# MCU2.net
KiCad netlist of a schematic drawn in Altium Designer
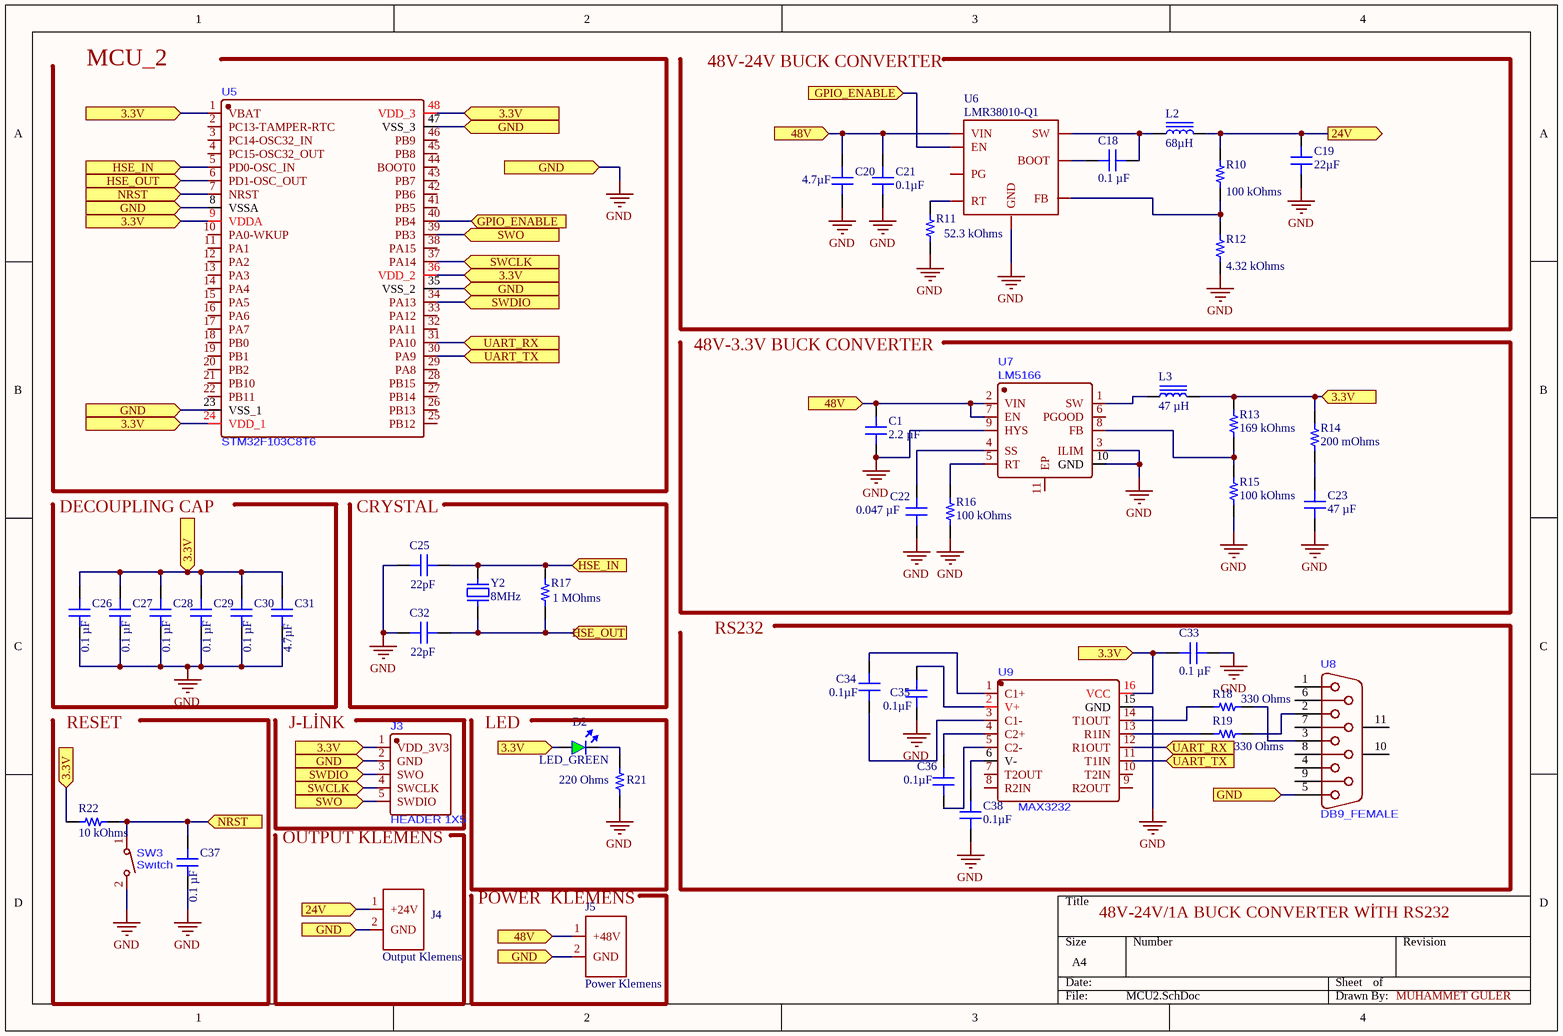
[diagram p0: MCU2.SchDoc]

(export (version "E")
  (design (tool "Eeschema 10.0.6"))
  (components
    (comp (ref "C1")
      (value "2.2 µF")
      (footprint "CAP 1210_3225 - 1MM")
      (description "CAP CER 2.2UF 100V X7R 1210")
      (fields
        (field (name "PART NUMBER") "1210BB225K101NGX085T")
        (field (name "MANUFACTURER") "Knowles Novacap")
      )
      (libsource (lib "Celestial Altium Library - altium_library") (part "Capacitor"))
    )
    (comp (ref "C18")
      (value "0.1 µF")
      (footprint "CAP 0603_1608")
      (description "CAP CER 0.1UF 50V X7R 0603")
      (fields (field (name "PART NUMBER") "C0603C104K5RAC7411"))
      (libsource (lib "Celestial Altium Library - altium_library") (part "Capacitor"))
    )
    (comp (ref "C19")
      (value "22µF")
      (footprint "CAP 1210_3225 - 2.8MM")
      (description "CAP CER 22UF 25V X5R 1210")
      (fields (field (name "PART NUMBER") "12103D226KAT2A") (field (name "MANUFACTURER") "AVX Corporation"))
      (libsource (lib "Celestial Altium Library - altium_library") (part "Capacitor"))
    )
    (comp (ref "C20")
      (value "4.7µF")
      (footprint "CAP 1210_3225 - 2.8MM")
      (description "CAP CER 4.7UF 100V X7R 1210")
      (fields (field (name "PART NUMBER") "12101C475K4T2A") (field (name "MANUFACTURER") "AVX Corporation"))
      (libsource (lib "Celestial Altium Library - altium_library") (part "Capacitor"))
    )
    (comp (ref "C21")
      (value "0.1µF")
      (footprint "CAP 0603_1608")
      (description "CAP CER 0.1UF 50V X7R 0603")
      (fields (field (name "PART NUMBER") "06035C104MAT2A") (field (name "MANUFACTURER") "AVX Corporation"))
      (libsource (lib "Celestial Altium Library - altium_library") (part "Capacitor"))
    )
    (comp (ref "C22")
      (value "0.047 µF")
      (footprint "CAP 0402_1005")
      (description "CAP CER 0402 47NF 16V X7R 10%")
      (fields (field (name "PART NUMBER") "C0402C473K3REC7867") (field (name "MANUFACTURER") "KEMET"))
      (libsource (lib "Celestial Altium Library - altium_library") (part "Capacitor"))
    )
    (comp (ref "C23")
      (value "47 µF")
      (footprint "CAP 1210_3225 - 1MM")
      (description "CAP CER 47UF 10V X5R 1210")
      (fields (field (name "PART NUMBER") "885012109007") (field (name "MANUFACTURER") "Würth Elektronik"))
      (libsource (lib "Celestial Altium Library - altium_library") (part "Capacitor"))
    )
    (comp (ref "C25")
      (value "22pF")
      (footprint "CAP 0603_1608")
      (description "CAP CER 22PF 6.3V NP0 0603")
      (fields (field (name "PART NUMBER") "06036A220J4T2A"))
      (libsource (lib "Celestial Altium Library - altium_library") (part "Capacitor"))
    )
    (comp (ref "C26")
      (value "0.1 µF")
      (footprint "CAP 0603_1608")
      (description "CAP CER 0.1UF 6.3V X7R 0603")
      (fields (field (name "PART NUMBER") "6R3X14W104MV4T"))
      (libsource (lib "Celestial Altium Library - altium_library") (part "Capacitor"))
    )
    (comp (ref "C27")
      (value "0.1 µF")
      (footprint "CAP 0603_1608")
      (description "CAP CER 0.1UF 6.3V X7R 0603")
      (fields (field (name "PART NUMBER") "6R3X14W104MV4T"))
      (libsource (lib "Celestial Altium Library - altium_library") (part "Capacitor"))
    )
    (comp (ref "C28")
      (value "0.1 µF")
      (footprint "CAP 0603_1608")
      (description "CAP CER 0.1UF 6.3V X7R 0603")
      (fields (field (name "PART NUMBER") "6R3X14W104MV4T"))
      (libsource (lib "Celestial Altium Library - altium_library") (part "Capacitor"))
    )
    (comp (ref "C29")
      (value "0.1 µF")
      (footprint "CAP 0603_1608")
      (description "CAP CER 0.1UF 6.3V X7R 0603")
      (fields (field (name "PART NUMBER") "6R3X14W104MV4T"))
      (libsource (lib "Celestial Altium Library - altium_library") (part "Capacitor"))
    )
    (comp (ref "C30")
      (value "0.1 µF")
      (footprint "CAP 0603_1608")
      (description "CAP CER 0.1UF 6.3V X7R 0603")
      (fields (field (name "PART NUMBER") "6R3X14W104MV4T"))
      (libsource (lib "Celestial Altium Library - altium_library") (part "Capacitor"))
    )
    (comp (ref "C31")
      (value "4.7µF")
      (footprint "CAP 0603_1608")
      (description "CAP CER 4.7UF 6.3V X5R 0603")
      (fields (field (name "PART NUMBER") "06036D475KAT4A"))
      (libsource (lib "Celestial Altium Library - altium_library") (part "Capacitor"))
    )
    (comp (ref "C32")
      (value "22pF")
      (footprint "CAP 0603_1608")
      (description "CAP CER 22PF 6.3V NP0 0603")
      (fields (field (name "PART NUMBER") "06036A220J4T2A"))
      (libsource (lib "Celestial Altium Library - altium_library") (part "Capacitor"))
    )
    (comp (ref "C33")
      (value "0.1 µF")
      (footprint "CAP 0603_1608")
      (description "CAP CER 0.1UF 6.3V X7R 0603")
      (fields
        (field (name "PART NUMBER") "6R3X14W104MV4T")
        (field (name "MANUFACTURER") "Johanson Dielectrics Inc.")
      )
      (libsource (lib "Celestial Altium Library - altium_library") (part "Capacitor"))
    )
    (comp (ref "C34")
      (value "0.1µF")
      (footprint "CAP 0603_1608")
      (description "CAP CER 0.1UF 16V X7R 0603")
      (fields (field (name "PART NUMBER") "0603YC104MAT2A") (field (name "MANUFACTURER") "AVX Corporation"))
      (libsource (lib "Celestial Altium Library - altium_library") (part "Capacitor"))
    )
    (comp (ref "C35")
      (value "0.1µF")
      (footprint "CAP 0603_1608")
      (description "CAP CER 0.1UF 16V X7R 0603")
      (fields (field (name "PART NUMBER") "0603YC104MAT2A") (field (name "MANUFACTURER") "AVX Corporation"))
      (libsource (lib "Celestial Altium Library - altium_library") (part "Capacitor"))
    )
    (comp (ref "C36")
      (value "0.1µF")
      (footprint "CAP 0603_1608")
      (description "CAP CER 0.1UF 16V X7R 0603")
      (fields (field (name "PART NUMBER") "0603YC104MAT2A") (field (name "MANUFACTURER") "AVX Corporation"))
      (libsource (lib "Celestial Altium Library - altium_library") (part "Capacitor"))
    )
    (comp (ref "C37")
      (value "0.1 µF")
      (footprint "CAP 0603_1608")
      (description "CAP CER 0.1UF 6.3V X7R 0603")
      (fields (field (name "PART NUMBER") "6R3X14W104MV4T"))
      (libsource (lib "Celestial Altium Library - altium_library") (part "Capacitor"))
    )
    (comp (ref "C38")
      (value "0.1µF")
      (footprint "CAP 0603_1608")
      (description "CAP CER 0.1UF 16V X7R 0603")
      (fields (field (name "PART NUMBER") "0603YC104MAT2A") (field (name "MANUFACTURER") "AVX Corporation"))
      (libsource (lib "Celestial Altium Library - altium_library") (part "Capacitor"))
    )
    (comp (ref "D2")
      (value "LED_GREEN")
      (footprint "LED_GREEN")
      (libsource (lib "Schlib1") (part "LED_GREEN"))
    )
    (comp (ref "J3")
      (value "HEADER 1X5")
      (footprint "1X5-PIN-HEADER-2.54MM_ES")
      (libsource (lib "Schlib1") (part "HEADER 1X5 COPY"))
    )
    (comp (ref "J4")
      (value "Output Klemens")
      (footprint "PCBComponent_1")
      (libsource (lib "Schlib1") (part "Output Klemens"))
    )
    (comp (ref "J5")
      (value "Power Klemens")
      (footprint "PCBComponent_1")
      (libsource (lib "Schlib1") (part "Power Klemens"))
    )
    (comp (ref "L2")
      (value "68µH")
      (footprint "WURTH WE-LQS 6045")
      (description "FIXED IND 68UH 1A 289 MOHM SMD")
      (fields (field (name "PART NUMBER") "74404064680"))
      (libsource (lib "Celestial Altium Library - altium_library") (part "Inductor"))
    )
    (comp (ref "L3")
      (value "47 µH")
      (footprint "TAIYO YUDEN NRS8030")
      (description "FIXED IND 47UH 1.3A 221 MOHM SMD")
      (fields (field (name "PART NUMBER") "NRS8030T470MJGJ") (field (name "MANUFACTURER") "Taiyo Yuden"))
      (libsource (lib "Celestial Altium Library - altium_library") (part "Inductor"))
    )
    (comp (ref "R10")
      (value "100 kOhms")
      (footprint "RES 0603_1608")
      (description "RES SMD 100K OHM 0.1% 1/16W 0603")
      (fields (field (name "PART NUMBER") "CPF0603B100KE"))
      (libsource (lib "Celestial Altium Library - altium_library") (part "Resistor"))
    )
    (comp (ref "R11")
      (value "52.3 kOhms")
      (footprint "RES 0603_1608")
      (description "RES SMD 52.3KOHM 0.5% 1/10W 0603")
      (fields (field (name "PART NUMBER") "RT0603DRE0752K3L"))
      (libsource (lib "Celestial Altium Library - altium_library") (part "Resistor"))
    )
    (comp (ref "R12")
      (value "4.32 kOhms")
      (footprint "RES 0603_1608")
      (description "RES SMD 4.32K OHM 0.1% 1/5W 0603")
      (fields (field (name "PART NUMBER") "ERJ-PB3B4321V"))
      (libsource (lib "Celestial Altium Library - altium_library") (part "Resistor"))
    )
    (comp (ref "R13")
      (value "169 kOhms")
      (footprint "RES 0402_1005")
      (description "RES 169K OHM 1% 1/16W 0402")
      (fields (field (name "PART NUMBER") "RC0402FR-07169KL") (field (name "MANUFACTURER") "Yageo"))
      (libsource (lib "Celestial Altium Library - altium_library") (part "Resistor"))
    )
    (comp (ref "R14")
      (value "200 mOhms")
      (footprint "RES 0402_1005")
      (description "RES 0.2 OHM 1% 1/16W 0402")
      (fields
        (field (name "PART NUMBER") "MFL0402R2000FP")
        (field (name "MANUFACTURER") "Eaton - Electronics Division")
      )
      (libsource (lib "Celestial Altium Library - altium_library") (part "Resistor"))
    )
    (comp (ref "R15")
      (value "100 kOhms")
      (footprint "RES 0402_1005")
      (description "RES SMD 100K OHM 5% 1/16W 0402")
      (fields (field (name "PART NUMBER") "AC0402JR-07100KL") (field (name "MANUFACTURER") "Yageo"))
      (libsource (lib "Celestial Altium Library - altium_library") (part "Resistor"))
    )
    (comp (ref "R16")
      (value "100 kOhms")
      (footprint "RES 0402_1005")
      (description "RES SMD 100K OHM 5% 1/16W 0402")
      (fields (field (name "PART NUMBER") "AC0402JR-07100KL") (field (name "MANUFACTURER") "Yageo"))
      (libsource (lib "Celestial Altium Library - altium_library") (part "Resistor"))
    )
    (comp (ref "R17")
      (value "1 MOhms")
      (footprint "RES 0603_1608")
      (description "RES SMD 1M OHM 1% 1/10W 0603")
      (fields (field (name "PART NUMBER") "RT0603FRE071ML"))
      (libsource (lib "Celestial Altium Library - altium_library") (part "Resistor"))
    )
    (comp (ref "R18")
      (value "330 Ohms")
      (footprint "RES 0603_1608")
      (description "RES SMD 330 OHM 1% 1/5W 0603")
      (fields
        (field (name "PART NUMBER") "CRGH0603F330R")
        (field (name "MANUFACTURER") "TE Connectivity Passive Product")
      )
      (libsource (lib "Celestial Altium Library - altium_library") (part "Resistor"))
    )
    (comp (ref "R19")
      (value "330 Ohms")
      (footprint "RES 0603_1608")
      (description "RES SMD 330 OHM 1% 1/5W 0603")
      (fields
        (field (name "PART NUMBER") "CRGH0603F330R")
        (field (name "MANUFACTURER") "TE Connectivity Passive Product")
      )
      (libsource (lib "Celestial Altium Library - altium_library") (part "Resistor"))
    )
    (comp (ref "R21")
      (value "220 Ohms")
      (footprint "RES 0603_1608")
      (description "RES SMD 220 OHM 5% 1/3W 0603")
      (fields (field (name "PART NUMBER") "CRCW0603220RJNEAHP") (field (name "MANUFACTURER") "Vishay Dale"))
      (libsource (lib "Celestial Altium Library - altium_library") (part "Resistor"))
    )
    (comp (ref "R22")
      (value "10 kOhms")
      (footprint "RES 0603_1608")
      (description "RES 10K OHM 0.1% 1/16W 0603")
      (fields
        (field (name "PART NUMBER") "RNCS0603BKE10K0")
        (field (name "MANUFACTURER") "Stackpole Electronics Inc")
      )
      (libsource (lib "Celestial Altium Library - altium_library") (part "Resistor"))
    )
    (comp (ref "SW3")
      (value "Swıtch")
      (footprint "SW-SMD_L4.0-W3.0-LS5.0")
      (libsource (lib "Schlib1") (part "Swıtch"))
    )
    (comp (ref "U5")
      (value "STM32F103C8T6")
      (footprint "UFQFPN-48_STM32")
      (libsource (lib "Schlib1") (part "STM32F103C8T6"))
    )
    (comp (ref "U6")
      (value "LMR38010-Q1")
      (footprint "LMR38010-Q1")
      (libsource (lib "Schlib1") (part "LMR38010-Q1"))
    )
    (comp (ref "U7")
      (value "LM5166")
      (footprint "VSON-10_L3.0-W3.0-P0.50-TL-EP-1")
      (libsource (lib "Schlib1") (part "LM5166DRCR"))
    )
    (comp (ref "U8")
      (value "DB9_FEMALE")
      (footprint "DB9-TH_DB9F_C5164093")
      (libsource (lib "Schlib1") (part "5745781-4"))
    )
    (comp (ref "U9")
      (value "MAX3232")
      (footprint "SOP-16_L9.9-W3.9-P1.27-LS6.0-BL")
      (libsource (lib "Schlib1") (part "MAX3232ESE-MS"))
    )
    (comp (ref "Y2")
      (value "8MHz")
      (footprint "NDK NX8045GB")
      (description "CRYSTAL 8.0000MHZ 8PF SMD")
      (fields
        (field (name "PART NUMBER") "NX8045GB-8.000M-STD-CSF-4")
        (field (name "MANUFACTURER") "NDK America, Inc.")
      )
      (libsource (lib "Celestial Altium Library - altium_library") (part "NDK Crystal NX8045GB"))
    )
  )
  (nets
    (net (code "1") (name "/3.3V") (class "Default")
      (node (ref "C26") (pin "2") (pinfunction "2_2") (pintype "passive"))
      (node (ref "C27") (pin "2") (pinfunction "2_2") (pintype "passive"))
      (node (ref "C28") (pin "2") (pinfunction "2_2") (pintype "passive"))
      (node (ref "C29") (pin "2") (pinfunction "2_2") (pintype "passive"))
      (node (ref "C30") (pin "2") (pinfunction "2_2") (pintype "passive"))
      (node (ref "C31") (pin "2") (pinfunction "2_2") (pintype "passive"))
      (node (ref "C33") (pin "2") (pinfunction "2_2") (pintype "passive"))
      (node (ref "D2") (pin "1") (pinfunction "IN_1") (pintype "passive"))
      (node (ref "J3") (pin "1") (pinfunction "VDD_3V3_1") (pintype "passive"))
      (node (ref "L3") (pin "2") (pinfunction "2_2") (pintype "passive"))
      (node (ref "R13") (pin "2") (pinfunction "2_2") (pintype "passive"))
      (node (ref "R14") (pin "2") (pinfunction "2_2") (pintype "passive"))
      (node (ref "R22") (pin "1") (pinfunction "1_1") (pintype "passive"))
      (node (ref "U5") (pin "1") (pinfunction "VBAT_1") (pintype "passive"))
      (node (ref "U5") (pin "24") (pinfunction "VDD_1_24") (pintype "passive"))
      (node (ref "U5") (pin "36") (pinfunction "VDD_2_36") (pintype "passive"))
      (node (ref "U5") (pin "48") (pinfunction "VDD_3_48") (pintype "passive"))
      (node (ref "U5") (pin "9") (pinfunction "VDDA_9") (pintype "passive"))
      (node (ref "U9") (pin "16") (pinfunction "VCC_16") (pintype "passive"))
    )
    (net (code "2") (name "/24V") (class "Default")
      (node (ref "C19") (pin "2") (pinfunction "2_2") (pintype "passive"))
      (node (ref "J4") (pin "1") (pinfunction "+24V_1") (pintype "passive"))
      (node (ref "L2") (pin "2") (pinfunction "2_2") (pintype "passive"))
      (node (ref "R10") (pin "2") (pinfunction "2_2") (pintype "passive"))
    )
    (net (code "3") (name "/48V") (class "Default")
      (node (ref "C1") (pin "2") (pinfunction "2_2") (pintype "passive"))
      (node (ref "C20") (pin "2") (pinfunction "2_2") (pintype "passive"))
      (node (ref "C21") (pin "2") (pinfunction "2_2") (pintype "passive"))
      (node (ref "J5") (pin "1") (pinfunction "+48V_1") (pintype "passive"))
      (node (ref "U6") (pin "3") (pinfunction "VIN_3") (pintype "passive"))
      (node (ref "U7") (pin "2") (pinfunction "VIN_2") (pintype "passive"))
      (node (ref "U7") (pin "7") (pinfunction "EN_7") (pintype "passive"))
    )
    (net (code "4") (name "/GPIO_ENABLE") (class "Default")
      (node (ref "U5") (pin "40") (pinfunction "PB4_40") (pintype "passive"))
      (node (ref "U6") (pin "2") (pinfunction "EN_2") (pintype "passive"))
    )
    (net (code "5") (name "/HSE_IN") (class "Default")
      (node (ref "C25") (pin "2") (pinfunction "2_2") (pintype "passive"))
      (node (ref "R17") (pin "2") (pinfunction "2_2") (pintype "passive"))
      (node (ref "U5") (pin "5") (pinfunction "PD0-OSC_IN_5") (pintype "passive"))
      (node (ref "Y2") (pin "2") (pinfunction "2_2") (pintype "passive"))
    )
    (net (code "6") (name "/HSE_OUT") (class "Default")
      (node (ref "C32") (pin "2") (pinfunction "2_2") (pintype "passive"))
      (node (ref "R17") (pin "1") (pinfunction "1_1") (pintype "passive"))
      (node (ref "U5") (pin "6") (pinfunction "PD1-OSC_OUT_6") (pintype "passive"))
      (node (ref "Y2") (pin "1") (pinfunction "1_1") (pintype "passive"))
    )
    (net (code "7") (name "/NRST") (class "Default")
      (node (ref "C37") (pin "2") (pinfunction "2_2") (pintype "passive"))
      (node (ref "R22") (pin "2") (pinfunction "2_2") (pintype "passive"))
      (node (ref "SW3") (pin "1") (pinfunction "1_1") (pintype "passive"))
      (node (ref "U5") (pin "7") (pinfunction "NRST_7") (pintype "passive"))
    )
    (net (code "8") (name "/SWCLK") (class "Default")
      (node (ref "J3") (pin "4") (pinfunction "SWCLK_4") (pintype "passive"))
      (node (ref "U5") (pin "37") (pinfunction "PA14_37") (pintype "passive"))
    )
    (net (code "9") (name "/SWDIO") (class "Default")
      (node (ref "J3") (pin "3") (pinfunction "SWO_3") (pintype "passive"))
      (node (ref "U5") (pin "34") (pinfunction "PA13_34") (pintype "passive"))
    )
    (net (code "10") (name "/SWO") (class "Default")
      (node (ref "J3") (pin "5") (pinfunction "SWDIO_5") (pintype "passive"))
      (node (ref "U5") (pin "39") (pinfunction "PB3_39") (pintype "passive"))
    )
    (net (code "11") (name "/UART_RX") (class "Default")
      (node (ref "U5") (pin "31") (pinfunction "PA10_31") (pintype "passive"))
      (node (ref "U9") (pin "12") (pinfunction "R1OUT_12") (pintype "passive"))
    )
    (net (code "12") (name "/UART_TX") (class "Default")
      (node (ref "U5") (pin "30") (pinfunction "PA9_30") (pintype "passive"))
      (node (ref "U9") (pin "11") (pinfunction "T1IN_11") (pintype "passive"))
    )
    (net (code "13") (name "GND") (class "Default")
      (node (ref "C1") (pin "1") (pinfunction "1_1") (pintype "passive"))
      (node (ref "C19") (pin "1") (pinfunction "1_1") (pintype "passive"))
      (node (ref "C20") (pin "1") (pinfunction "1_1") (pintype "passive"))
      (node (ref "C21") (pin "1") (pinfunction "1_1") (pintype "passive"))
      (node (ref "C22") (pin "1") (pinfunction "1_1") (pintype "passive"))
      (node (ref "C23") (pin "1") (pinfunction "1_1") (pintype "passive"))
      (node (ref "C25") (pin "1") (pinfunction "1_1") (pintype "passive"))
      (node (ref "C26") (pin "1") (pinfunction "1_1") (pintype "passive"))
      (node (ref "C27") (pin "1") (pinfunction "1_1") (pintype "passive"))
      (node (ref "C28") (pin "1") (pinfunction "1_1") (pintype "passive"))
      (node (ref "C29") (pin "1") (pinfunction "1_1") (pintype "passive"))
      (node (ref "C30") (pin "1") (pinfunction "1_1") (pintype "passive"))
      (node (ref "C31") (pin "1") (pinfunction "1_1") (pintype "passive"))
      (node (ref "C32") (pin "1") (pinfunction "1_1") (pintype "passive"))
      (node (ref "C33") (pin "1") (pinfunction "1_1") (pintype "passive"))
      (node (ref "C35") (pin "1") (pinfunction "1_1") (pintype "passive"))
      (node (ref "C37") (pin "1") (pinfunction "1_1") (pintype "passive"))
      (node (ref "C38") (pin "1") (pinfunction "1_1") (pintype "passive"))
      (node (ref "J3") (pin "2") (pinfunction "GND_2") (pintype "passive"))
      (node (ref "J4") (pin "2") (pinfunction "GND_2") (pintype "passive"))
      (node (ref "J5") (pin "2") (pinfunction "GND_2") (pintype "passive"))
      (node (ref "R11") (pin "1") (pinfunction "1_1") (pintype "passive"))
      (node (ref "R12") (pin "1") (pinfunction "1_1") (pintype "passive"))
      (node (ref "R15") (pin "1") (pinfunction "1_1") (pintype "passive"))
      (node (ref "R16") (pin "1") (pinfunction "1_1") (pintype "passive"))
      (node (ref "R21") (pin "1") (pinfunction "1_1") (pintype "passive"))
      (node (ref "SW3") (pin "2") (pinfunction "2_2") (pintype "passive"))
      (node (ref "U5") (pin "23") (pinfunction "VSS_1_23") (pintype "passive"))
      (node (ref "U5") (pin "35") (pinfunction "VSS_2_35") (pintype "passive"))
      (node (ref "U5") (pin "47") (pinfunction "VSS_3_47") (pintype "passive"))
      (node (ref "U5") (pin "8") (pinfunction "VSSA_8") (pintype "passive"))
      (node (ref "U6") (pin "1") (pinfunction "GND_1") (pintype "passive"))
      (node (ref "U7") (pin "10") (pinfunction "GND_10") (pintype "passive"))
      (node (ref "U7") (pin "3") (pinfunction "ILIM_3") (pintype "passive"))
      (node (ref "U7") (pin "9") (pinfunction "HYS_9") (pintype "passive"))
      (node (ref "U8") (pin "5") (pinfunction "5_5") (pintype "passive"))
      (node (ref "U9") (pin "15") (pinfunction "GND_15") (pintype "passive"))
    )
    (net (code "14") (name "Net-(C23-Pad2)") (class "Default")
      (node (ref "C23") (pin "2") (pinfunction "2_2") (pintype "passive"))
      (node (ref "R14") (pin "1") (pinfunction "1_1") (pintype "passive"))
    )
    (net (code "15") (name "Net-(D2-OUT)") (class "Default")
      (node (ref "D2") (pin "2") (pinfunction "OUT_2") (pintype "passive"))
      (node (ref "R21") (pin "2") (pinfunction "2_2") (pintype "passive"))
    )
    (net (code "16") (name "Net-(R18-Pad2)") (class "Default")
      (node (ref "R18") (pin "2") (pinfunction "2_2") (pintype "passive"))
      (node (ref "U8") (pin "3") (pinfunction "3_3") (pintype "passive"))
    )
    (net (code "17") (name "Net-(R19-Pad2)") (class "Default")
      (node (ref "R19") (pin "2") (pinfunction "2_2") (pintype "passive"))
      (node (ref "U8") (pin "2") (pinfunction "2_2") (pintype "passive"))
    )
    (net (code "18") (name "Net-(U6-BOOT)") (class "Default")
      (node (ref "C18") (pin "2") (pinfunction "2_2") (pintype "passive"))
      (node (ref "U6") (pin "7") (pinfunction "BOOT_7") (pintype "passive"))
    )
    (net (code "19") (name "Net-(U6-FB)") (class "Default")
      (node (ref "R10") (pin "1") (pinfunction "1_1") (pintype "passive"))
      (node (ref "R12") (pin "2") (pinfunction "2_2") (pintype "passive"))
      (node (ref "U6") (pin "5") (pinfunction "FB_5") (pintype "passive"))
    )
    (net (code "20") (name "Net-(U6-RT)") (class "Default")
      (node (ref "R11") (pin "2") (pinfunction "2_2") (pintype "passive"))
      (node (ref "U6") (pin "4") (pinfunction "RT_4") (pintype "passive"))
    )
    (net (code "21") (name "Net-(U6-SW)") (class "Default")
      (node (ref "C18") (pin "1") (pinfunction "1_1") (pintype "passive"))
      (node (ref "L2") (pin "1") (pinfunction "1_1") (pintype "passive"))
      (node (ref "U6") (pin "8") (pinfunction "SW_8") (pintype "passive"))
    )
    (net (code "22") (name "Net-(U7-FB)") (class "Default")
      (node (ref "R13") (pin "1") (pinfunction "1_1") (pintype "passive"))
      (node (ref "R15") (pin "2") (pinfunction "2_2") (pintype "passive"))
      (node (ref "U7") (pin "8") (pinfunction "FB_8") (pintype "passive"))
    )
    (net (code "23") (name "Net-(U7-RT)") (class "Default")
      (node (ref "R16") (pin "2") (pinfunction "2_2") (pintype "passive"))
      (node (ref "U7") (pin "5") (pinfunction "RT_5") (pintype "passive"))
    )
    (net (code "24") (name "Net-(U7-SS)") (class "Default")
      (node (ref "C22") (pin "2") (pinfunction "2_2") (pintype "passive"))
      (node (ref "U7") (pin "4") (pinfunction "SS_4") (pintype "passive"))
    )
    (net (code "25") (name "Net-(U7-SW)") (class "Default")
      (node (ref "L3") (pin "1") (pinfunction "1_1") (pintype "passive"))
      (node (ref "U7") (pin "1") (pinfunction "SW_1") (pintype "passive"))
    )
    (net (code "26") (name "Net-(U9-C1+)") (class "Default")
      (node (ref "C34") (pin "2") (pinfunction "2_2") (pintype "passive"))
      (node (ref "U9") (pin "1") (pinfunction "C1+_1") (pintype "passive"))
    )
    (net (code "27") (name "Net-(U9-C1-)") (class "Default")
      (node (ref "C34") (pin "1") (pinfunction "1_1") (pintype "passive"))
      (node (ref "U9") (pin "3") (pinfunction "C1-_3") (pintype "passive"))
    )
    (net (code "28") (name "Net-(U9-C2+)") (class "Default")
      (node (ref "C36") (pin "2") (pinfunction "2_2") (pintype "passive"))
      (node (ref "U9") (pin "4") (pinfunction "C2+_4") (pintype "passive"))
    )
    (net (code "29") (name "Net-(U9-C2-)") (class "Default")
      (node (ref "C36") (pin "1") (pinfunction "1_1") (pintype "passive"))
      (node (ref "U9") (pin "5") (pinfunction "C2-_5") (pintype "passive"))
    )
    (net (code "30") (name "Net-(U9-R1IN)") (class "Default")
      (node (ref "R19") (pin "1") (pinfunction "1_1") (pintype "passive"))
      (node (ref "U9") (pin "13") (pinfunction "R1IN_13") (pintype "passive"))
    )
    (net (code "31") (name "Net-(U9-T1OUT)") (class "Default")
      (node (ref "R18") (pin "1") (pinfunction "1_1") (pintype "passive"))
      (node (ref "U9") (pin "14") (pinfunction "T1OUT_14") (pintype "passive"))
    )
    (net (code "32") (name "Net-(U9-V+)") (class "Default")
      (node (ref "C35") (pin "2") (pinfunction "2_2") (pintype "passive"))
      (node (ref "U9") (pin "2") (pinfunction "V+_2") (pintype "passive"))
    )
    (net (code "33") (name "Net-(U9-V-)") (class "Default")
      (node (ref "C38") (pin "2") (pinfunction "2_2") (pintype "passive"))
      (node (ref "U9") (pin "6") (pinfunction "V-_6") (pintype "passive"))
    )
    (net (code "34") (name "unconnected-(U5-BOOT0-Pad44)") (class "Default")
      (node (ref "U5") (pin "44") (pinfunction "BOOT0_44") (pintype "passive"))
    )
    (net (code "35") (name "unconnected-(U5-PA0-WKUP-Pad10)") (class "Default")
      (node (ref "U5") (pin "10") (pinfunction "PA0-WKUP_10") (pintype "passive"))
    )
    (net (code "36") (name "unconnected-(U5-PA1-Pad11)") (class "Default")
      (node (ref "U5") (pin "11") (pinfunction "PA1_11") (pintype "passive"))
    )
    (net (code "37") (name "unconnected-(U5-PA2-Pad12)") (class "Default")
      (node (ref "U5") (pin "12") (pinfunction "PA2_12") (pintype "passive"))
    )
    (net (code "38") (name "unconnected-(U5-PA3-Pad13)") (class "Default")
      (node (ref "U5") (pin "13") (pinfunction "PA3_13") (pintype "passive"))
    )
    (net (code "39") (name "unconnected-(U5-PA4-Pad14)") (class "Default")
      (node (ref "U5") (pin "14") (pinfunction "PA4_14") (pintype "passive"))
    )
    (net (code "40") (name "unconnected-(U5-PA5-Pad15)") (class "Default")
      (node (ref "U5") (pin "15") (pinfunction "PA5_15") (pintype "passive"))
    )
    (net (code "41") (name "unconnected-(U5-PA6-Pad16)") (class "Default")
      (node (ref "U5") (pin "16") (pinfunction "PA6_16") (pintype "passive"))
    )
    (net (code "42") (name "unconnected-(U5-PA7-Pad17)") (class "Default")
      (node (ref "U5") (pin "17") (pinfunction "PA7_17") (pintype "passive"))
    )
    (net (code "43") (name "unconnected-(U5-PA8-Pad29)") (class "Default")
      (node (ref "U5") (pin "29") (pinfunction "PA8_29") (pintype "passive"))
    )
    (net (code "44") (name "unconnected-(U5-PA11-Pad32)") (class "Default")
      (node (ref "U5") (pin "32") (pinfunction "PA11_32") (pintype "passive"))
    )
    (net (code "45") (name "unconnected-(U5-PA12-Pad33)") (class "Default")
      (node (ref "U5") (pin "33") (pinfunction "PA12_33") (pintype "passive"))
    )
    (net (code "46") (name "unconnected-(U5-PA15-Pad38)") (class "Default")
      (node (ref "U5") (pin "38") (pinfunction "PA15_38") (pintype "passive"))
    )
    (net (code "47") (name "unconnected-(U5-PB0-Pad18)") (class "Default")
      (node (ref "U5") (pin "18") (pinfunction "PB0_18") (pintype "passive"))
    )
    (net (code "48") (name "unconnected-(U5-PB1-Pad19)") (class "Default")
      (node (ref "U5") (pin "19") (pinfunction "PB1_19") (pintype "passive"))
    )
    (net (code "49") (name "unconnected-(U5-PB2-Pad20)") (class "Default")
      (node (ref "U5") (pin "20") (pinfunction "PB2_20") (pintype "passive"))
    )
    (net (code "50") (name "unconnected-(U5-PB5-Pad41)") (class "Default")
      (node (ref "U5") (pin "41") (pinfunction "PB5_41") (pintype "passive"))
    )
    (net (code "51") (name "unconnected-(U5-PB6-Pad42)") (class "Default")
      (node (ref "U5") (pin "42") (pinfunction "PB6_42") (pintype "passive"))
    )
    (net (code "52") (name "unconnected-(U5-PB7-Pad43)") (class "Default")
      (node (ref "U5") (pin "43") (pinfunction "PB7_43") (pintype "passive"))
    )
    (net (code "53") (name "unconnected-(U5-PB8-Pad45)") (class "Default")
      (node (ref "U5") (pin "45") (pinfunction "PB8_45") (pintype "passive"))
    )
    (net (code "54") (name "unconnected-(U5-PB9-Pad46)") (class "Default")
      (node (ref "U5") (pin "46") (pinfunction "PB9_46") (pintype "passive"))
    )
    (net (code "55") (name "unconnected-(U5-PB10-Pad21)") (class "Default")
      (node (ref "U5") (pin "21") (pinfunction "PB10_21") (pintype "passive"))
    )
    (net (code "56") (name "unconnected-(U5-PB11-Pad22)") (class "Default")
      (node (ref "U5") (pin "22") (pinfunction "PB11_22") (pintype "passive"))
    )
    (net (code "57") (name "unconnected-(U5-PB12-Pad25)") (class "Default")
      (node (ref "U5") (pin "25") (pinfunction "PB12_25") (pintype "passive"))
    )
    (net (code "58") (name "unconnected-(U5-PB13-Pad26)") (class "Default")
      (node (ref "U5") (pin "26") (pinfunction "PB13_26") (pintype "passive"))
    )
    (net (code "59") (name "unconnected-(U5-PB14-Pad27)") (class "Default")
      (node (ref "U5") (pin "27") (pinfunction "PB14_27") (pintype "passive"))
    )
    (net (code "60") (name "unconnected-(U5-PB15-Pad28)") (class "Default")
      (node (ref "U5") (pin "28") (pinfunction "PB15_28") (pintype "passive"))
    )
    (net (code "61") (name "unconnected-(U5-PC13-TAMPER-RTC-Pad2)") (class "Default")
      (node (ref "U5") (pin "2") (pinfunction "PC13-TAMPER-RTC_2") (pintype "passive"))
    )
    (net (code "62") (name "unconnected-(U5-PC14-OSC32_IN-Pad3)") (class "Default")
      (node (ref "U5") (pin "3") (pinfunction "PC14-OSC32_IN_3") (pintype "passive"))
    )
    (net (code "63") (name "unconnected-(U5-PC15-OSC32_OUT-Pad4)") (class "Default")
      (node (ref "U5") (pin "4") (pinfunction "PC15-OSC32_OUT_4") (pintype "passive"))
    )
    (net (code "64") (name "unconnected-(U6-PG-Pad6)") (class "Default")
      (node (ref "U6") (pin "6") (pinfunction "PG_6") (pintype "passive"))
    )
    (net (code "65") (name "unconnected-(U7-EP-Pad11)") (class "Default")
      (node (ref "U7") (pin "11") (pinfunction "EP_11") (pintype "passive"))
    )
    (net (code "66") (name "unconnected-(U7-PGOOD-Pad6)") (class "Default")
      (node (ref "U7") (pin "6") (pinfunction "PGOOD_6") (pintype "passive"))
    )
    (net (code "67") (name "unconnected-(U8-MH1-Pad10)") (class "Default")
      (node (ref "U8") (pin "10") (pinfunction "MH1_10") (pintype "passive"))
    )
    (net (code "68") (name "unconnected-(U8-MH2-Pad11)") (class "Default")
      (node (ref "U8") (pin "11") (pinfunction "MH2_11") (pintype "passive"))
    )
    (net (code "69") (name "unconnected-(U8-Pad1)") (class "Default")
      (node (ref "U8") (pin "1") (pinfunction "1_1") (pintype "passive"))
    )
    (net (code "70") (name "unconnected-(U8-Pad4)") (class "Default")
      (node (ref "U8") (pin "4") (pinfunction "4_4") (pintype "passive"))
    )
    (net (code "71") (name "unconnected-(U8-Pad6)") (class "Default")
      (node (ref "U8") (pin "6") (pinfunction "6_6") (pintype "passive"))
    )
    (net (code "72") (name "unconnected-(U8-Pad7)") (class "Default")
      (node (ref "U8") (pin "7") (pinfunction "7_7") (pintype "passive"))
    )
    (net (code "73") (name "unconnected-(U8-Pad8)") (class "Default")
      (node (ref "U8") (pin "8") (pinfunction "8_8") (pintype "passive"))
    )
    (net (code "74") (name "unconnected-(U8-Pad9)") (class "Default")
      (node (ref "U8") (pin "9") (pinfunction "9_9") (pintype "passive"))
    )
    (net (code "75") (name "unconnected-(U9-R2IN-Pad8)") (class "Default")
      (node (ref "U9") (pin "8") (pinfunction "R2IN_8") (pintype "passive"))
    )
    (net (code "76") (name "unconnected-(U9-R2OUT-Pad9)") (class "Default")
      (node (ref "U9") (pin "9") (pinfunction "R2OUT_9") (pintype "passive"))
    )
    (net (code "77") (name "unconnected-(U9-T2IN-Pad10)") (class "Default")
      (node (ref "U9") (pin "10") (pinfunction "T2IN_10") (pintype "passive"))
    )
    (net (code "78") (name "unconnected-(U9-T2OUT-Pad7)") (class "Default")
      (node (ref "U9") (pin "7") (pinfunction "T2OUT_7") (pintype "passive"))
    )
  )
)
